# Temp_Sensor_Unit.net
KiCad netlist of a schematic drawn in Altium Designer
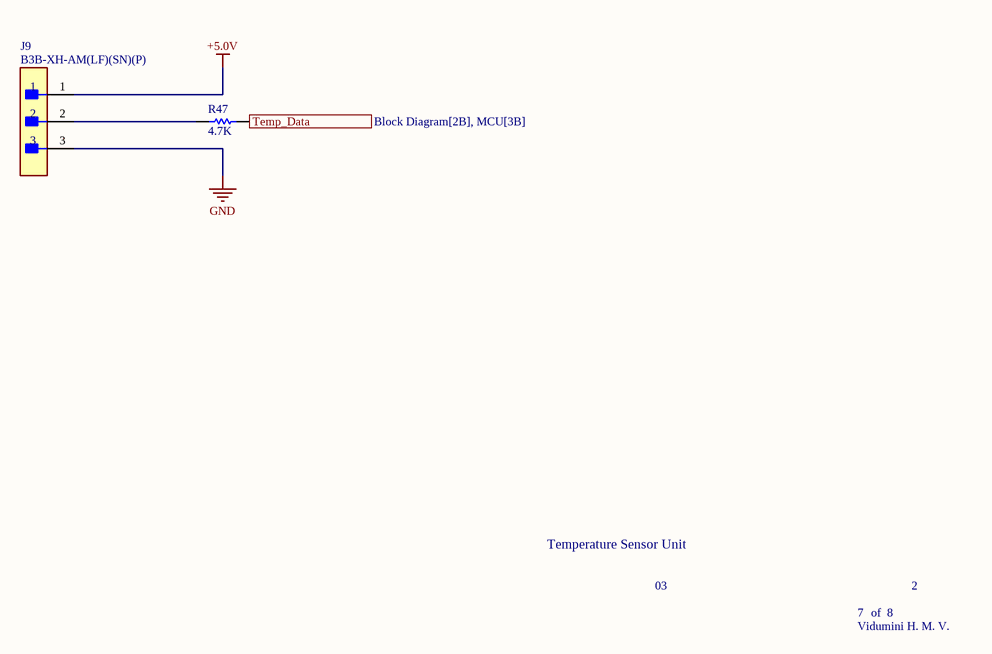
[diagram p0: Temp Sensor Unit.SchDoc]

(export (version "E")
  (design (tool "Eeschema 10.0.6"))
  (components
    (comp (ref "J9")
      (value "B3B-XH-AM(LF)(SN)(P)")
      (footprint "FP-B3B-XH-AM_LF_SN_P-MFG")
      (description "CONN HEADER VERT 3POS 2.5MM")
      (libsource (lib "Altium Content Vault") (part "0d3f023dd272f625e17a2be33dea85f"))
    )
    (comp (ref "R47")
      (value "4.7K")
      (footprint "RESC3216X60X45ML15T20")
      (description "Chip Resistor, 4.7 KOhm, +/- 1%, 0.25 W, -55 to 155 degC, 1206 (3216 Metric), RoHS, Tape and Reel")
      (fields (field (name "MANUFACTURER") "Vishay Semiconductor") (field (name "TOLERANCE") "1%"))
      (libsource (lib "Altium Content Vault") (part "RES-2"))
    )
  )
  (nets
    (net (code "1") (name "+5.0V") (class "Default")
      (node (ref "J9") (pin "1") (pinfunction "1_1") (pintype "passive"))
    )
    (net (code "2") (name "/Temp_Data") (class "Default")
      (node (ref "R47") (pin "1") (pinfunction "1_1") (pintype "passive"))
    )
    (net (code "3") (name "GND") (class "Default")
      (node (ref "J9") (pin "3") (pinfunction "3_3") (pintype "passive"))
    )
    (net (code "4") (name "Net-(J9-Pad2)") (class "Default")
      (node (ref "J9") (pin "2") (pinfunction "2_2") (pintype "passive"))
      (node (ref "R47") (pin "2") (pinfunction "2_2") (pintype "passive"))
    )
  )
)
